# ProPrj_cdweatherv2_2026-01-21.net
KiCad netlist of a schematic drawn in EasyEDA Pro
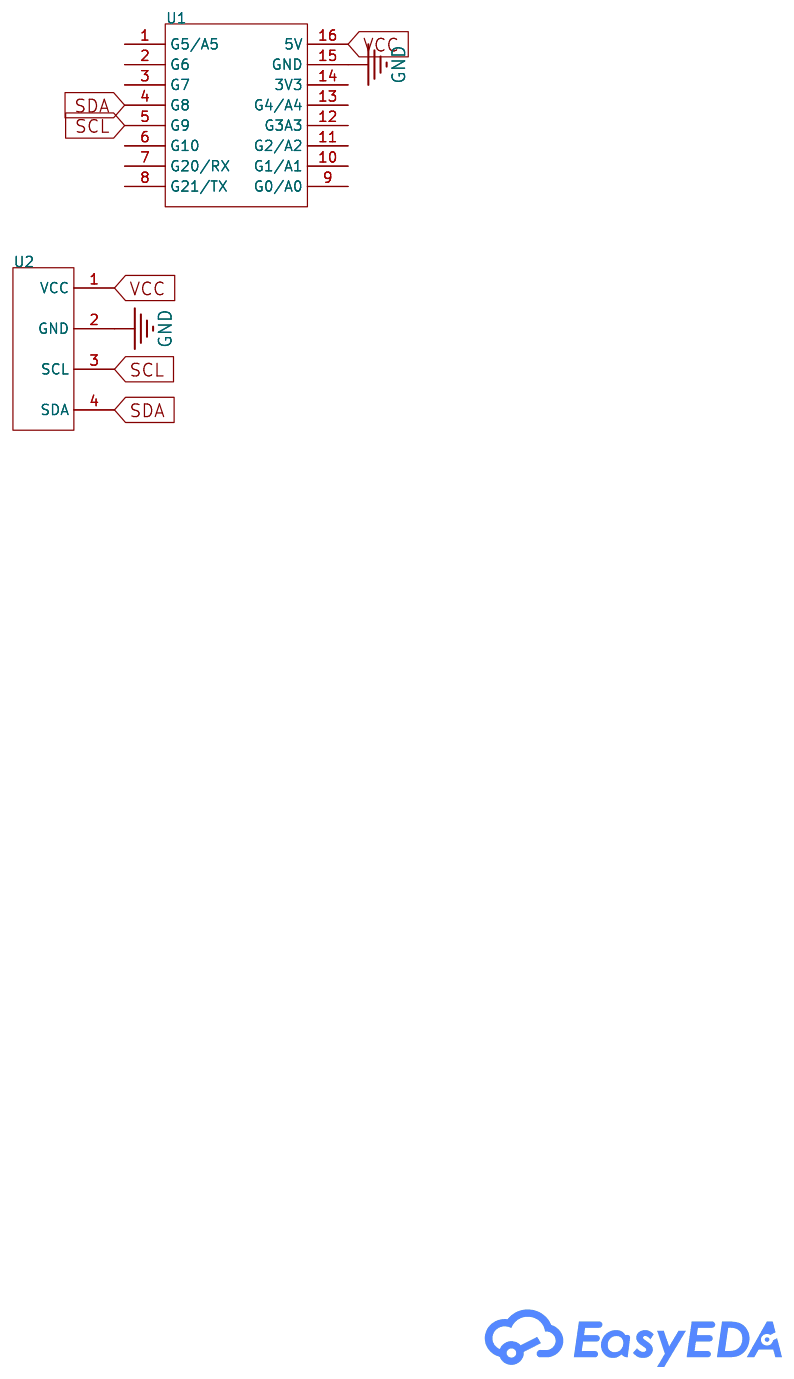
[diagram p0: schematic sheet]

(export (version "E")
  (design (tool "Eeschema 10.0.6"))
  (components
    (comp (ref "U1")
      (value "~")
      (footprint "easyedapro:ESP32 C3 SUPER MINI")
      (libsource (lib "easyedapro") (part "ESP32 C3 SUPER MINI"))
    )
    (comp (ref "U2")
      (value "~")
      (footprint "easyedapro:BME280 Module - V")
      (libsource (lib "easyedapro") (part "BME280 Module - V"))
    )
  )
  (nets
    (net (code "1") (name "GND") (class "Default")
      (node (ref "U1") (pin "15") (pinfunction "GND_15") (pintype "input"))
      (node (ref "U2") (pin "2") (pinfunction "GND_2") (pintype "input"))
    )
    (net (code "2") (name "SCL") (class "Default")
      (node (ref "U1") (pin "5") (pinfunction "G9_5") (pintype "input"))
      (node (ref "U2") (pin "3") (pinfunction "SCL_3") (pintype "input"))
    )
    (net (code "3") (name "SDA") (class "Default")
      (node (ref "U1") (pin "4") (pinfunction "G8_4") (pintype "input"))
      (node (ref "U2") (pin "4") (pinfunction "SDA_4") (pintype "input"))
    )
    (net (code "4") (name "VCC") (class "Default")
      (node (ref "U1") (pin "16") (pinfunction "5V_16") (pintype "input"))
      (node (ref "U2") (pin "1") (pinfunction "VCC_1") (pintype "input"))
    )
    (net (code "5") (name "unconnected-(U1-3V3-Pad14)") (class "Default")
      (node (ref "U1") (pin "14") (pinfunction "3V3_14") (pintype "input"))
    )
    (net (code "6") (name "unconnected-(U1-G0{slash}A0-Pad9)") (class "Default")
      (node (ref "U1") (pin "9") (pinfunction "G0/A0_9") (pintype "input"))
    )
    (net (code "7") (name "unconnected-(U1-G1{slash}A1-Pad10)") (class "Default")
      (node (ref "U1") (pin "10") (pinfunction "G1/A1_10") (pintype "input"))
    )
    (net (code "8") (name "unconnected-(U1-G2{slash}A2-Pad11)") (class "Default")
      (node (ref "U1") (pin "11") (pinfunction "G2/A2_11") (pintype "input"))
    )
    (net (code "9") (name "unconnected-(U1-G3A3-Pad12)") (class "Default")
      (node (ref "U1") (pin "12") (pinfunction "G3A3_12") (pintype "input"))
    )
    (net (code "10") (name "unconnected-(U1-G4{slash}A4-Pad13)") (class "Default")
      (node (ref "U1") (pin "13") (pinfunction "G4/A4_13") (pintype "input"))
    )
    (net (code "11") (name "unconnected-(U1-G5{slash}A5-Pad1)") (class "Default")
      (node (ref "U1") (pin "1") (pinfunction "G5/A5_1") (pintype "input"))
    )
    (net (code "12") (name "unconnected-(U1-G6-Pad2)") (class "Default")
      (node (ref "U1") (pin "2") (pinfunction "G6_2") (pintype "input"))
    )
    (net (code "13") (name "unconnected-(U1-G7-Pad3)") (class "Default")
      (node (ref "U1") (pin "3") (pinfunction "G7_3") (pintype "input"))
    )
    (net (code "14") (name "unconnected-(U1-G10-Pad6)") (class "Default")
      (node (ref "U1") (pin "6") (pinfunction "G10_6") (pintype "input"))
    )
    (net (code "15") (name "unconnected-(U1-G20{slash}RX-Pad7)") (class "Default")
      (node (ref "U1") (pin "7") (pinfunction "G20/RX_7") (pintype "input"))
    )
    (net (code "16") (name "unconnected-(U1-G21{slash}TX-Pad8)") (class "Default")
      (node (ref "U1") (pin "8") (pinfunction "G21/TX_8") (pintype "input"))
    )
  )
)
